# 2_Controler.net
KiCad netlist of a schematic drawn in Altium Designer
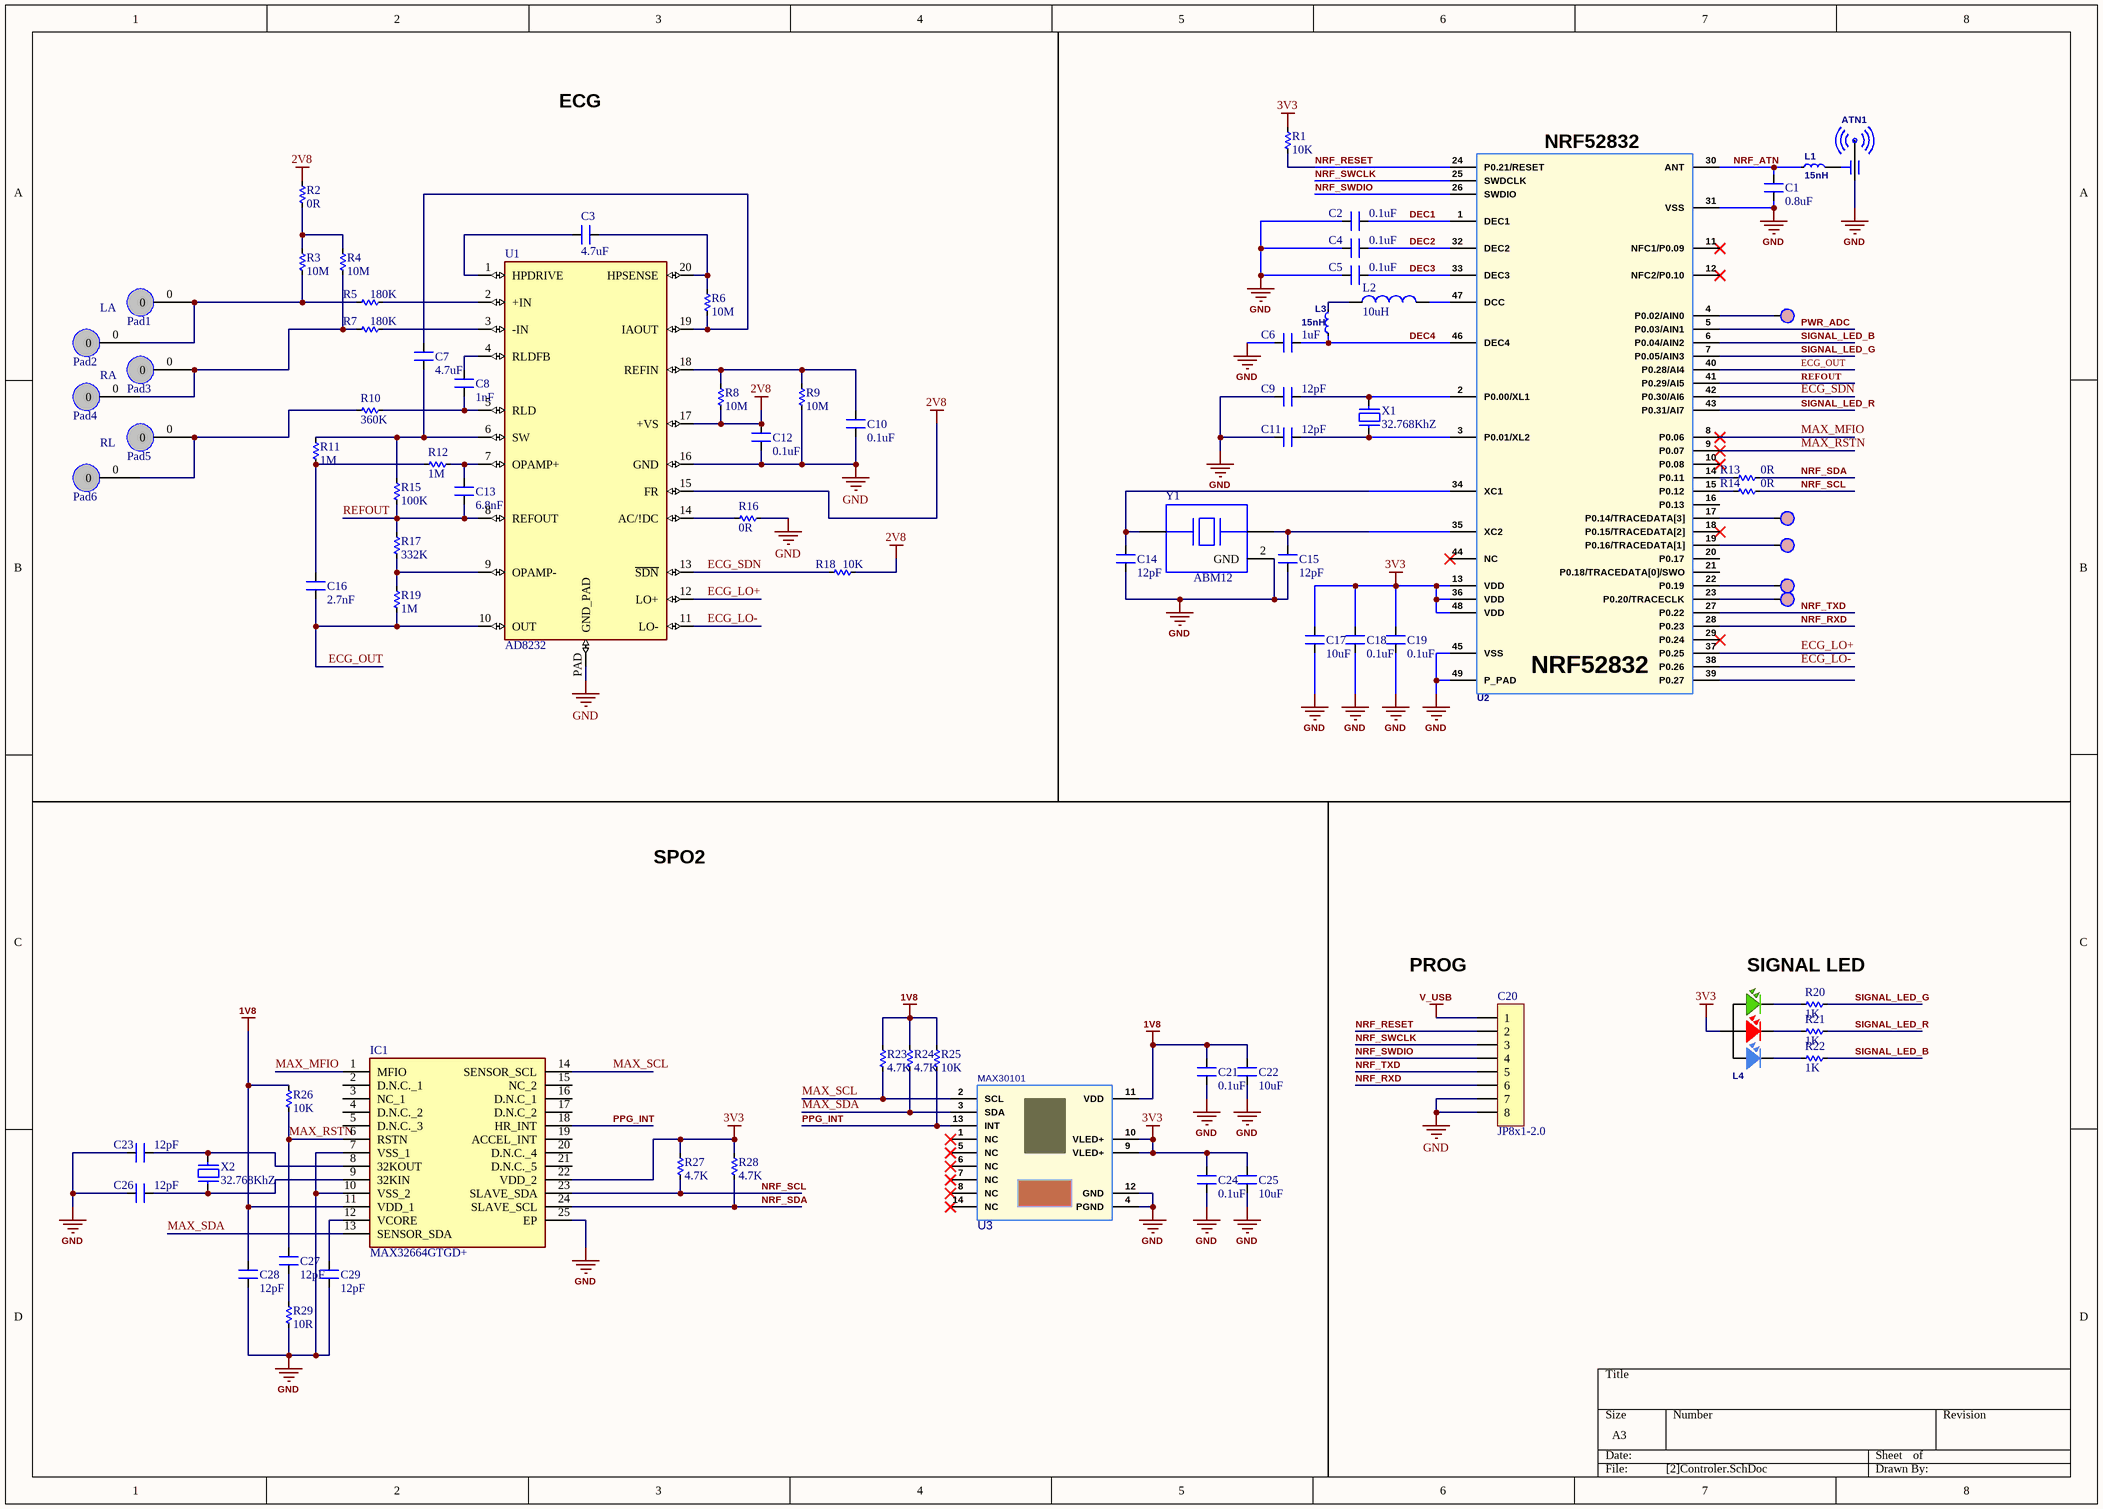
[diagram p0: [2]Controler.SchDoc]

(export (version "E")
  (design (tool "Eeschema 10.0.6"))
  (components
    (comp (ref "ATN1")
      (value "P-ANT")
      (footprint "Antenna 2G4")
      (libsource (lib "VitalSignal EcgPpg Board") (part "P-ANT"))
    )
    (comp (ref "C1")
      (value "0.8uF")
      (footprint "CN-SMD-0603")
      (description "Tu gom")
      (libsource (lib "LIBTanCN") (part "CN"))
    )
    (comp (ref "C2")
      (value "0.1uF")
      (footprint "CN-SMD-0603")
      (description "Tu gom")
      (libsource (lib "LIBTanCN") (part "CN"))
    )
    (comp (ref "C3")
      (value "4.7uF")
      (footprint "CN-SMD-0603")
      (description "Tu gom")
      (libsource (lib "LIBTanCN") (part "CN"))
    )
    (comp (ref "C4")
      (value "0.1uF")
      (footprint "CN-SMD-0603")
      (description "Tu gom")
      (libsource (lib "LIBTanCN") (part "CN"))
    )
    (comp (ref "C5")
      (value "0.1uF")
      (footprint "CN-SMD-0603")
      (description "Tu gom")
      (libsource (lib "LIBTanCN") (part "CN"))
    )
    (comp (ref "C6")
      (value "1uF")
      (footprint "CN-SMD-0603")
      (description "Tu gom")
      (libsource (lib "LIBTanCN") (part "CN"))
    )
    (comp (ref "C7")
      (value "4.7uF")
      (footprint "CN-SMD-0603")
      (description "Tu gom")
      (libsource (lib "LIBTanCN") (part "CN"))
    )
    (comp (ref "C8")
      (value "1nF")
      (footprint "CN-SMD-0603")
      (description "Tu gom")
      (libsource (lib "LIBTanCN") (part "CN"))
    )
    (comp (ref "C9")
      (value "12pF")
      (footprint "CN-SMD-0603")
      (description "Tu gom")
      (libsource (lib "LIBTanCN") (part "CN"))
    )
    (comp (ref "C10")
      (value "0.1uF")
      (footprint "CN-SMD-0603")
      (description "Tu gom")
      (libsource (lib "LIBTanCN") (part "CN"))
    )
    (comp (ref "C11")
      (value "12pF")
      (footprint "CN-SMD-0603")
      (description "Tu gom")
      (libsource (lib "LIBTanCN") (part "CN"))
    )
    (comp (ref "C12")
      (value "0.1uF")
      (footprint "CN-SMD-0603")
      (description "Tu gom")
      (libsource (lib "LIBTanCN") (part "CN"))
    )
    (comp (ref "C13")
      (value "6.8nF")
      (footprint "CN-SMD-0603")
      (description "Tu gom")
      (libsource (lib "LIBTanCN") (part "CN"))
    )
    (comp (ref "C14")
      (value "12pF")
      (footprint "CN-SMD-0603")
      (description "Tu gom")
      (libsource (lib "LIBTanCN") (part "CN"))
    )
    (comp (ref "C15")
      (value "12pF")
      (footprint "CN-SMD-0603")
      (description "Tu gom")
      (libsource (lib "LIBTanCN") (part "CN"))
    )
    (comp (ref "C16")
      (value "2.7nF")
      (footprint "CN-SMD-0603")
      (description "Tu gom")
      (libsource (lib "LIBTanCN") (part "CN"))
    )
    (comp (ref "C17")
      (value "10uF")
      (footprint "CN-SMD-0603")
      (description "Tu gom")
      (libsource (lib "LIBTanCN") (part "CN"))
    )
    (comp (ref "C18")
      (value "0.1uF")
      (footprint "CN-SMD-0603")
      (description "Tu gom")
      (libsource (lib "LIBTanCN") (part "CN"))
    )
    (comp (ref "C19")
      (value "0.1uF")
      (footprint "CN-SMD-0603")
      (description "Tu gom")
      (libsource (lib "LIBTanCN") (part "CN"))
    )
    (comp (ref "C20")
      (value "JP8x1-2.0")
      (footprint "J8-D1T")
      (description "WR-PHD 2.00 mm Socket Header")
      (fields
        (field (name "MANUFACTURER") "Würth Elektronik eiSos GmbH")
        (field (name "PARTNO") "62000811821")
        (field (name "CREATED BY") "Karrer Zheng")
      )
      (libsource (lib "LIBRARY") (part "JP8x1-2.0"))
    )
    (comp (ref "C21")
      (value "0.1uF")
      (footprint "CN-SMD-0603")
      (description "Tu gom")
      (libsource (lib "LIBTanCN") (part "CN"))
    )
    (comp (ref "C22")
      (value "10uF")
      (footprint "CN-SMD-0603")
      (description "Tu gom")
      (libsource (lib "LIBTanCN") (part "CN"))
    )
    (comp (ref "C23")
      (value "12pF")
      (footprint "CN-SMD-0603")
      (description "Tu gom")
      (libsource (lib "LIBTanCN") (part "CN"))
    )
    (comp (ref "C24")
      (value "0.1uF")
      (footprint "CN-SMD-0603")
      (description "Tu gom")
      (libsource (lib "LIBTanCN") (part "CN"))
    )
    (comp (ref "C25")
      (value "10uF")
      (footprint "CN-SMD-0603")
      (description "Tu gom")
      (libsource (lib "LIBTanCN") (part "CN"))
    )
    (comp (ref "C26")
      (value "12pF")
      (footprint "CN-SMD-0603")
      (description "Tu gom")
      (libsource (lib "LIBTanCN") (part "CN"))
    )
    (comp (ref "C27")
      (value "12pF")
      (footprint "CN-SMD-0603")
      (description "Tu gom")
      (libsource (lib "LIBTanCN") (part "CN"))
    )
    (comp (ref "C28")
      (value "12pF")
      (footprint "CN-SMD-0603")
      (description "Tu gom")
      (libsource (lib "LIBTanCN") (part "CN"))
    )
    (comp (ref "C29")
      (value "12pF")
      (footprint "CN-SMD-0603")
      (description "Tu gom")
      (libsource (lib "LIBTanCN") (part "CN"))
    )
    (comp (ref "IC1")
      (value "MAX32664GTGD+")
      (footprint "SamacSys:MAX32664GTGD")
      (description "Integrated Circuit")
      (fields (field (name "MOUSER PART NUMBER") "700-MAX32664GTGD+"))
      (libsource (lib "SamacSys") (part "MAX32664GTGD+"))
    )
    (comp (ref "L1")
      (value "15nH")
      (footprint "P-INDC-0402INDC1005X60N EIA")
      (libsource (lib "VitalSignal EcgPpg Board") (part "P-INDC-0603"))
    )
    (comp (ref "L2")
      (value "10uH")
      (footprint "Inductor_0603:INDC1608X95N")
      (description "Ind Chip Shielded Multi-Layer 10uH 30% 1MHz Ferrite 50mA 0603 T/R")
      (fields (field (name "MP") "ASMCI-0603-100N-T"))
      (libsource (lib "Inductor_0603") (part "ASMCI-0603-100N-T"))
    )
    (comp (ref "L3")
      (value "15nH")
      (footprint "P-INDC-0402INDC1005X60N EIA")
      (libsource (lib "VitalSignal EcgPpg Board") (part "P-INDC-0603"))
    )
    (comp (ref "L4")
      (value "Led RGB 0603 Anot")
      (footprint "Led RGB 0603 Anode")
      (libsource (lib "Lib_Nhat_2019") (part "Led RGB 0603 Anot"))
    )
    (comp (ref "Pad1")
      (value "LA")
      (footprint "PcbLib1:pad_ecg")
      (description "pad_ecg")
      (libsource (lib "Schlib1") (part "pad_ecg"))
    )
    (comp (ref "Pad2")
      (value "LA")
      (footprint "PcbLib1:pad_ecg")
      (description "pad_ecg")
      (libsource (lib "Schlib1") (part "pad_ecg"))
    )
    (comp (ref "Pad3")
      (value "RA")
      (footprint "PcbLib1:pad_ecg")
      (description "pad_ecg")
      (libsource (lib "Schlib1") (part "pad_ecg"))
    )
    (comp (ref "Pad4")
      (value "pad_ecg")
      (footprint "PcbLib1:pad_ecg")
      (libsource (lib "Schlib1") (part "pad_ecg"))
    )
    (comp (ref "Pad5")
      (value "RL")
      (footprint "PcbLib1:pad_ecg")
      (description "pad_ecg")
      (libsource (lib "Schlib1") (part "pad_ecg"))
    )
    (comp (ref "Pad6")
      (value "pad_ecg")
      (footprint "PcbLib1:pad_ecg")
      (libsource (lib "Schlib1") (part "pad_ecg"))
    )
    (comp (ref "R1")
      (value "10K")
      (footprint "RES-SMD-0603")
      (description "Resistor")
      (fields
        (field (name "MANUFACTURER") "Generic Components")
        (field (name "PUBLISHER") "Altium Hobart Technology Centre")
      )
      (libsource (lib "LIBRARY") (part "Res-SMD"))
    )
    (comp (ref "R2")
      (value "0R")
      (footprint "RES-SMD-0603")
      (description "Resistor")
      (fields
        (field (name "MANUFACTURER") "Generic Components")
        (field (name "PUBLISHER") "Altium Hobart Technology Centre")
      )
      (libsource (lib "LIBRARY") (part "Res-SMD"))
    )
    (comp (ref "R3")
      (value "10M")
      (footprint "RES-SMD-0603")
      (description "Resistor")
      (fields
        (field (name "MANUFACTURER") "Generic Components")
        (field (name "PUBLISHER") "Altium Hobart Technology Centre")
      )
      (libsource (lib "LIBRARY") (part "Res-SMD"))
    )
    (comp (ref "R4")
      (value "10M")
      (footprint "RES-SMD-0603")
      (description "Resistor")
      (fields
        (field (name "MANUFACTURER") "Generic Components")
        (field (name "PUBLISHER") "Altium Hobart Technology Centre")
      )
      (libsource (lib "LIBRARY") (part "Res-SMD"))
    )
    (comp (ref "R5")
      (value "180K")
      (footprint "RES-SMD-0603")
      (description "Resistor")
      (fields
        (field (name "MANUFACTURER") "Generic Components")
        (field (name "PUBLISHER") "Altium Hobart Technology Centre")
      )
      (libsource (lib "LIBRARY") (part "Res-SMD"))
    )
    (comp (ref "R6")
      (value "10M")
      (footprint "RES-SMD-0603")
      (description "Resistor")
      (fields
        (field (name "MANUFACTURER") "Generic Components")
        (field (name "PUBLISHER") "Altium Hobart Technology Centre")
      )
      (libsource (lib "LIBRARY") (part "Res-SMD"))
    )
    (comp (ref "R7")
      (value "180K")
      (footprint "RES-SMD-0603")
      (description "Resistor")
      (fields
        (field (name "MANUFACTURER") "Generic Components")
        (field (name "PUBLISHER") "Altium Hobart Technology Centre")
      )
      (libsource (lib "LIBRARY") (part "Res-SMD"))
    )
    (comp (ref "R8")
      (value "10M")
      (footprint "RES-SMD-0603")
      (description "Resistor")
      (fields
        (field (name "MANUFACTURER") "Generic Components")
        (field (name "PUBLISHER") "Altium Hobart Technology Centre")
      )
      (libsource (lib "LIBRARY") (part "Res-SMD"))
    )
    (comp (ref "R9")
      (value "10M")
      (footprint "RES-SMD-0603")
      (description "Resistor")
      (fields
        (field (name "MANUFACTURER") "Generic Components")
        (field (name "PUBLISHER") "Altium Hobart Technology Centre")
      )
      (libsource (lib "LIBRARY") (part "Res-SMD"))
    )
    (comp (ref "R10")
      (value "360K")
      (footprint "RES-SMD-0603")
      (description "Resistor")
      (fields
        (field (name "MANUFACTURER") "Generic Components")
        (field (name "PUBLISHER") "Altium Hobart Technology Centre")
      )
      (libsource (lib "LIBRARY") (part "Res-SMD"))
    )
    (comp (ref "R11")
      (value "1M")
      (footprint "RES-SMD-0603")
      (description "Resistor")
      (fields
        (field (name "MANUFACTURER") "Generic Components")
        (field (name "PUBLISHER") "Altium Hobart Technology Centre")
      )
      (libsource (lib "LIBRARY") (part "Res-SMD"))
    )
    (comp (ref "R12")
      (value "1M")
      (footprint "RES-SMD-0603")
      (description "Resistor")
      (fields
        (field (name "MANUFACTURER") "Generic Components")
        (field (name "PUBLISHER") "Altium Hobart Technology Centre")
      )
      (libsource (lib "LIBRARY") (part "Res-SMD"))
    )
    (comp (ref "R13")
      (value "0R")
      (footprint "RES-SMD-0603")
      (description "Resistor")
      (fields
        (field (name "MANUFACTURER") "Generic Components")
        (field (name "PUBLISHER") "Altium Hobart Technology Centre")
      )
      (libsource (lib "LIBRARY") (part "Res-SMD"))
    )
    (comp (ref "R14")
      (value "0R")
      (footprint "RES-SMD-0603")
      (description "Resistor")
      (fields
        (field (name "MANUFACTURER") "Generic Components")
        (field (name "PUBLISHER") "Altium Hobart Technology Centre")
      )
      (libsource (lib "LIBRARY") (part "Res-SMD"))
    )
    (comp (ref "R15")
      (value "100K")
      (footprint "RES-SMD-0603")
      (description "Resistor")
      (fields
        (field (name "MANUFACTURER") "Generic Components")
        (field (name "PUBLISHER") "Altium Hobart Technology Centre")
      )
      (libsource (lib "LIBRARY") (part "Res-SMD"))
    )
    (comp (ref "R16")
      (value "0R")
      (footprint "RES-SMD-0603")
      (description "Resistor")
      (fields
        (field (name "MANUFACTURER") "Generic Components")
        (field (name "PUBLISHER") "Altium Hobart Technology Centre")
      )
      (libsource (lib "LIBRARY") (part "Res-SMD"))
    )
    (comp (ref "R17")
      (value "332K")
      (footprint "RES-SMD-0603")
      (description "Resistor")
      (fields
        (field (name "MANUFACTURER") "Generic Components")
        (field (name "PUBLISHER") "Altium Hobart Technology Centre")
      )
      (libsource (lib "LIBRARY") (part "Res-SMD"))
    )
    (comp (ref "R18")
      (value "10K")
      (footprint "RES-SMD-0603")
      (description "Resistor")
      (fields
        (field (name "MANUFACTURER") "Generic Components")
        (field (name "PUBLISHER") "Altium Hobart Technology Centre")
      )
      (libsource (lib "LIBRARY") (part "Res-SMD"))
    )
    (comp (ref "R19")
      (value "1M")
      (footprint "RES-SMD-0603")
      (description "Resistor")
      (fields
        (field (name "MANUFACTURER") "Generic Components")
        (field (name "PUBLISHER") "Altium Hobart Technology Centre")
      )
      (libsource (lib "LIBRARY") (part "Res-SMD"))
    )
    (comp (ref "R20")
      (value "1K")
      (footprint "RES-SMD-0603")
      (description "Resistor")
      (fields
        (field (name "MANUFACTURER") "Generic Components")
        (field (name "PUBLISHER") "Altium Hobart Technology Centre")
      )
      (libsource (lib "LIBRARY") (part "Res-SMD"))
    )
    (comp (ref "R21")
      (value "1K")
      (footprint "RES-SMD-0603")
      (description "Resistor")
      (fields
        (field (name "MANUFACTURER") "Generic Components")
        (field (name "PUBLISHER") "Altium Hobart Technology Centre")
      )
      (libsource (lib "LIBRARY") (part "Res-SMD"))
    )
    (comp (ref "R22")
      (value "1K")
      (footprint "RES-SMD-0603")
      (description "Resistor")
      (fields
        (field (name "MANUFACTURER") "Generic Components")
        (field (name "PUBLISHER") "Altium Hobart Technology Centre")
      )
      (libsource (lib "LIBRARY") (part "Res-SMD"))
    )
    (comp (ref "R23")
      (value "4.7K")
      (footprint "RES-SMD-0603")
      (description "Resistor")
      (fields
        (field (name "MANUFACTURER") "Generic Components")
        (field (name "PUBLISHER") "Altium Hobart Technology Centre")
      )
      (libsource (lib "LIBRARY") (part "Res-SMD"))
    )
    (comp (ref "R24")
      (value "4.7K")
      (footprint "RES-SMD-0603")
      (description "Resistor")
      (fields
        (field (name "MANUFACTURER") "Generic Components")
        (field (name "PUBLISHER") "Altium Hobart Technology Centre")
      )
      (libsource (lib "LIBRARY") (part "Res-SMD"))
    )
    (comp (ref "R25")
      (value "10K")
      (footprint "RES-SMD-0603")
      (description "Resistor")
      (fields
        (field (name "MANUFACTURER") "Generic Components")
        (field (name "PUBLISHER") "Altium Hobart Technology Centre")
      )
      (libsource (lib "LIBRARY") (part "Res-SMD"))
    )
    (comp (ref "R26")
      (value "10K")
      (footprint "RES-SMD-0603")
      (description "Resistor")
      (fields
        (field (name "MANUFACTURER") "Generic Components")
        (field (name "PUBLISHER") "Altium Hobart Technology Centre")
      )
      (libsource (lib "LIBRARY") (part "Res-SMD"))
    )
    (comp (ref "R27")
      (value "4.7K")
      (footprint "RES-SMD-0603")
      (description "Resistor")
      (fields
        (field (name "MANUFACTURER") "Generic Components")
        (field (name "PUBLISHER") "Altium Hobart Technology Centre")
      )
      (libsource (lib "LIBRARY") (part "Res-SMD"))
    )
    (comp (ref "R28")
      (value "4.7K")
      (footprint "RES-SMD-0603")
      (description "Resistor")
      (fields
        (field (name "MANUFACTURER") "Generic Components")
        (field (name "PUBLISHER") "Altium Hobart Technology Centre")
      )
      (libsource (lib "LIBRARY") (part "Res-SMD"))
    )
    (comp (ref "R29")
      (value "10R")
      (footprint "RES-SMD-0603")
      (description "Resistor")
      (fields
        (field (name "MANUFACTURER") "Generic Components")
        (field (name "PUBLISHER") "Altium Hobart Technology Centre")
      )
      (libsource (lib "LIBRARY") (part "Res-SMD"))
    )
    (comp (ref "TP1")
      (value "TP")
      (footprint "P-TP 1MM")
      (libsource (lib "VitalSignal EcgPpg Board") (part "P-TESTPOINT"))
    )
    (comp (ref "TP2")
      (value "TP")
      (footprint "P-TP 1MM")
      (libsource (lib "VitalSignal EcgPpg Board") (part "P-TESTPOINT"))
    )
    (comp (ref "TP3")
      (value "TP")
      (footprint "P-TP 1MM")
      (libsource (lib "VitalSignal EcgPpg Board") (part "P-TESTPOINT"))
    )
    (comp (ref "TP4")
      (value "TP")
      (footprint "P-TP 1MM")
      (libsource (lib "VitalSignal EcgPpg Board") (part "P-TESTPOINT"))
    )
    (comp (ref "TP5")
      (value "TP")
      (footprint "P-TP 1MM")
      (libsource (lib "VitalSignal EcgPpg Board") (part "P-TESTPOINT"))
    )
    (comp (ref "U1")
      (value "AD8232")
      (footprint "AD8232:LFCSP_20")
      (description "ECG Front End 20-LFCSP-WQ _4x4_")
      (fields (field (name "MF") "Analog Devices"))
      (libsource (lib "AD8232") (part "AD8232"))
    )
    (comp (ref "U2")
      (value "Nrf52832")
      (footprint "QFN48_NRF52832")
      (description "BLE SoC")
      (libsource (lib "VitalSignal EcgPpg Board") (part "Nrf52832"))
    )
    (comp (ref "U3")
      (value "MAX30101")
      (footprint "MAX30101")
      (description "Pulse oximeter and Heart rate sensor")
      (libsource (lib "Lib_Nhat_2019") (part "MAX30101"))
    )
    (comp (ref "X1")
      (value "32.768KhZ")
      (footprint "XT2-32.768KHz-2_V")
      (description "Crystal, 32.768 KHz, -40 to 85 degC, 3.2 x 1.5 x 0.9 mm SMD")
      (libsource (lib "LIBRARY") (part "XT2"))
    )
    (comp (ref "X2")
      (value "32.768KhZ")
      (footprint "XT2-32.768KHz-2_V")
      (description "Crystal, 32.768 KHz, -40 to 85 degC, 3.2 x 1.5 x 0.9 mm SMD")
      (libsource (lib "LIBRARY") (part "XT2"))
    )
    (comp (ref "Y1")
      (value "ABM12")
      (footprint "DFN160X120X45-4N")
      (fields (field (name "MP") "ABM12-32.000MHZ-B2X-T3"))
      (libsource (lib "ABM12-32.000MHZ-B2X-T3") (part "ABM12-32.000MHZ-B2X-T3"))
    )
  )
  (nets
    (net (code "1") (name "/DEC1") (class "Default")
      (node (ref "C2") (pin "2") (pinfunction "2_2") (pintype "passive"))
      (node (ref "U2") (pin "1") (pinfunction "DEC1_1") (pintype "passive"))
    )
    (net (code "2") (name "/DEC2") (class "Default")
      (node (ref "C4") (pin "2") (pinfunction "2_2") (pintype "passive"))
      (node (ref "U2") (pin "32") (pinfunction "DEC2_32") (pintype "passive"))
    )
    (net (code "3") (name "/DEC3") (class "Default")
      (node (ref "C5") (pin "2") (pinfunction "2_2") (pintype "passive"))
      (node (ref "U2") (pin "33") (pinfunction "DEC3_33") (pintype "passive"))
    )
    (net (code "4") (name "/DEC4") (class "Default")
      (node (ref "C6") (pin "2") (pinfunction "2_2") (pintype "passive"))
      (node (ref "L3") (pin "1") (pinfunction "1_1") (pintype "passive"))
      (node (ref "U2") (pin "46") (pinfunction "DEC4_46") (pintype "passive"))
    )
    (net (code "5") (name "/ECG_LO+") (class "Default")
      (node (ref "U1") (pin "12") (pinfunction "LO+_12") (pintype "bidirectional"))
      (node (ref "U2") (pin "37") (pinfunction "P0.25_37") (pintype "passive"))
    )
    (net (code "6") (name "/ECG_LO-") (class "Default")
      (node (ref "U1") (pin "11") (pinfunction "LO-_11") (pintype "bidirectional"))
      (node (ref "U2") (pin "38") (pinfunction "P0.26_38") (pintype "passive"))
    )
    (net (code "7") (name "/ECG_OUT") (class "Default")
      (node (ref "C16") (pin "2") (pinfunction "2_2") (pintype "passive"))
      (node (ref "R19") (pin "1") (pinfunction "1_1") (pintype "passive"))
      (node (ref "U1") (pin "10") (pinfunction "OUT_10") (pintype "bidirectional"))
      (node (ref "U2") (pin "40") (pinfunction "P0.28/AI4_40") (pintype "passive"))
    )
    (net (code "8") (name "/ECG_SDN") (class "Default")
      (node (ref "R18") (pin "1") (pinfunction "1_1") (pintype "passive"))
      (node (ref "U1") (pin "13") (pinfunction "~{SDN}_13") (pintype "bidirectional"))
      (node (ref "U2") (pin "42") (pinfunction "P0.30/AI6_42") (pintype "passive"))
    )
    (net (code "9") (name "/MAX_MFIO") (class "Default")
      (node (ref "IC1") (pin "1") (pinfunction "MFIO_1") (pintype "passive"))
      (node (ref "U2") (pin "8") (pinfunction "P0.06_8") (pintype "passive"))
    )
    (net (code "10") (name "/MAX_RSTN") (class "Default")
      (node (ref "C27") (pin "1") (pinfunction "1_1") (pintype "passive"))
      (node (ref "IC1") (pin "6") (pinfunction "RSTN_6") (pintype "passive"))
      (node (ref "R26") (pin "1") (pinfunction "1_1") (pintype "passive"))
      (node (ref "U2") (pin "9") (pinfunction "P0.07_9") (pintype "passive"))
    )
    (net (code "11") (name "/MAX_SCL") (class "Default")
      (node (ref "IC1") (pin "14") (pinfunction "SENSOR_SCL_14") (pintype "passive"))
      (node (ref "R23") (pin "1") (pinfunction "1_1") (pintype "passive"))
      (node (ref "U3") (pin "2") (pinfunction "SCL_2") (pintype "passive"))
    )
    (net (code "12") (name "/MAX_SDA") (class "Default")
      (node (ref "IC1") (pin "13") (pinfunction "SENSOR_SDA_13") (pintype "passive"))
      (node (ref "R24") (pin "1") (pinfunction "1_1") (pintype "passive"))
      (node (ref "U3") (pin "3") (pinfunction "SDA_3") (pintype "passive"))
    )
    (net (code "13") (name "/NRF_ATN") (class "Default")
      (node (ref "C1") (pin "2") (pinfunction "2_2") (pintype "passive"))
      (node (ref "L1") (pin "1") (pinfunction "1_1") (pintype "passive"))
      (node (ref "U2") (pin "30") (pinfunction "ANT_30") (pintype "passive"))
    )
    (net (code "14") (name "/NRF_RESET") (class "Default")
      (node (ref "C20") (pin "2") (pinfunction "2_2") (pintype "passive"))
      (node (ref "R1") (pin "1") (pinfunction "1_1") (pintype "passive"))
      (node (ref "U2") (pin "24") (pinfunction "P0.21/RESET_24") (pintype "passive"))
    )
    (net (code "15") (name "/NRF_RXD") (class "Default")
      (node (ref "C20") (pin "6") (pinfunction "6_6") (pintype "passive"))
      (node (ref "U2") (pin "28") (pinfunction "P0.23_28") (pintype "passive"))
    )
    (net (code "16") (name "/NRF_SCL") (class "Default")
      (node (ref "IC1") (pin "23") (pinfunction "SLAVE_SDA_23") (pintype "passive"))
      (node (ref "R14") (pin "1") (pinfunction "1_1") (pintype "passive"))
      (node (ref "R27") (pin "1") (pinfunction "1_1") (pintype "passive"))
    )
    (net (code "17") (name "/NRF_SDA") (class "Default")
      (node (ref "IC1") (pin "24") (pinfunction "SLAVE_SCL_24") (pintype "passive"))
      (node (ref "R13") (pin "1") (pinfunction "1_1") (pintype "passive"))
      (node (ref "R28") (pin "1") (pinfunction "1_1") (pintype "passive"))
    )
    (net (code "18") (name "/NRF_SWCLK") (class "Default")
      (node (ref "C20") (pin "3") (pinfunction "3_3") (pintype "passive"))
      (node (ref "U2") (pin "25") (pinfunction "SWDCLK_25") (pintype "passive"))
    )
    (net (code "19") (name "/NRF_SWDIO") (class "Default")
      (node (ref "C20") (pin "4") (pinfunction "4_4") (pintype "passive"))
      (node (ref "U2") (pin "26") (pinfunction "SWDIO_26") (pintype "passive"))
    )
    (net (code "20") (name "/NRF_TXD") (class "Default")
      (node (ref "C20") (pin "5") (pinfunction "5_5") (pintype "passive"))
      (node (ref "U2") (pin "27") (pinfunction "P0.22_27") (pintype "passive"))
    )
    (net (code "21") (name "/PPG_INT") (class "Default")
      (node (ref "IC1") (pin "18") (pinfunction "HR_INT_18") (pintype "passive"))
      (node (ref "R25") (pin "1") (pinfunction "1_1") (pintype "passive"))
      (node (ref "U3") (pin "13") (pinfunction "INT_13") (pintype "passive"))
    )
    (net (code "22") (name "/PWR_ADC") (class "Default")
      (node (ref "U2") (pin "5") (pinfunction "P0.03/AIN1_5") (pintype "passive"))
    )
    (net (code "23") (name "/REFOUT") (class "Default")
      (node (ref "C13") (pin "2") (pinfunction "2_2") (pintype "passive"))
      (node (ref "R15") (pin "1") (pinfunction "1_1") (pintype "passive"))
      (node (ref "R17") (pin "2") (pinfunction "2_2") (pintype "passive"))
      (node (ref "U1") (pin "8") (pinfunction "REFOUT_8") (pintype "bidirectional"))
      (node (ref "U2") (pin "41") (pinfunction "P0.29/AI5_41") (pintype "passive"))
    )
    (net (code "24") (name "/SIGNAL_LED_B") (class "Default")
      (node (ref "R22") (pin "2") (pinfunction "2_2") (pintype "passive"))
      (node (ref "U2") (pin "6") (pinfunction "P0.04/AIN2_6") (pintype "passive"))
    )
    (net (code "25") (name "/SIGNAL_LED_G") (class "Default")
      (node (ref "R20") (pin "2") (pinfunction "2_2") (pintype "passive"))
      (node (ref "U2") (pin "7") (pinfunction "P0.05/AIN3_7") (pintype "passive"))
    )
    (net (code "26") (name "/SIGNAL_LED_R") (class "Default")
      (node (ref "R21") (pin "2") (pinfunction "2_2") (pintype "passive"))
      (node (ref "U2") (pin "43") (pinfunction "P0.31/AI7_43") (pintype "passive"))
    )
    (net (code "27") (name "1V8") (class "Default")
      (node (ref "C21") (pin "2") (pinfunction "2_2") (pintype "passive"))
      (node (ref "C22") (pin "2") (pinfunction "2_2") (pintype "passive"))
      (node (ref "C28") (pin "1") (pinfunction "1_1") (pintype "passive"))
      (node (ref "IC1") (pin "11") (pinfunction "VDD_1_11") (pintype "passive"))
      (node (ref "R23") (pin "2") (pinfunction "2_2") (pintype "passive"))
      (node (ref "R24") (pin "2") (pinfunction "2_2") (pintype "passive"))
      (node (ref "R25") (pin "2") (pinfunction "2_2") (pintype "passive"))
      (node (ref "R26") (pin "2") (pinfunction "2_2") (pintype "passive"))
      (node (ref "U3") (pin "11") (pinfunction "VDD_11") (pintype "passive"))
    )
    (net (code "28") (name "2V8") (class "Default")
      (node (ref "C12") (pin "2") (pinfunction "2_2") (pintype "passive"))
      (node (ref "R18") (pin "2") (pinfunction "2_2") (pintype "passive"))
      (node (ref "R2") (pin "1") (pinfunction "1_1") (pintype "passive"))
      (node (ref "R8") (pin "2") (pinfunction "2_2") (pintype "passive"))
      (node (ref "U1") (pin "15") (pinfunction "FR_15") (pintype "bidirectional"))
      (node (ref "U1") (pin "17") (pinfunction "+VS_17") (pintype "bidirectional"))
    )
    (net (code "29") (name "3V3") (class "Default")
      (node (ref "C17") (pin "1") (pinfunction "1_1") (pintype "passive"))
      (node (ref "C18") (pin "1") (pinfunction "1_1") (pintype "passive"))
      (node (ref "C19") (pin "1") (pinfunction "1_1") (pintype "passive"))
      (node (ref "C24") (pin "2") (pinfunction "2_2") (pintype "passive"))
      (node (ref "C25") (pin "2") (pinfunction "2_2") (pintype "passive"))
      (node (ref "IC1") (pin "22") (pinfunction "VDD_2_22") (pintype "passive"))
      (node (ref "L4") (pin "2") (pinfunction "2_2") (pintype "passive"))
      (node (ref "R1") (pin "2") (pinfunction "2_2") (pintype "passive"))
      (node (ref "R27") (pin "2") (pinfunction "2_2") (pintype "passive"))
      (node (ref "R28") (pin "2") (pinfunction "2_2") (pintype "passive"))
      (node (ref "U2") (pin "13") (pinfunction "VDD_13") (pintype "passive"))
      (node (ref "U2") (pin "36") (pinfunction "VDD_36") (pintype "passive"))
      (node (ref "U2") (pin "48") (pinfunction "VDD_48") (pintype "passive"))
      (node (ref "U3") (pin "10") (pinfunction "VLED+_10") (pintype "passive"))
      (node (ref "U3") (pin "9") (pinfunction "VLED+_9") (pintype "passive"))
    )
    (net (code "30") (name "GND") (class "Default")
      (node (ref "ATN1") (pin "1") (pinfunction "1_1") (pintype "passive"))
      (node (ref "C1") (pin "1") (pinfunction "1_1") (pintype "passive"))
      (node (ref "C10") (pin "1") (pinfunction "1_1") (pintype "passive"))
      (node (ref "C11") (pin "2") (pinfunction "2_2") (pintype "passive"))
      (node (ref "C12") (pin "1") (pinfunction "1_1") (pintype "passive"))
      (node (ref "C14") (pin "1") (pinfunction "1_1") (pintype "passive"))
      (node (ref "C15") (pin "1") (pinfunction "1_1") (pintype "passive"))
      (node (ref "C17") (pin "2") (pinfunction "2_2") (pintype "passive"))
      (node (ref "C18") (pin "2") (pinfunction "2_2") (pintype "passive"))
      (node (ref "C19") (pin "2") (pinfunction "2_2") (pintype "passive"))
      (node (ref "C2") (pin "1") (pinfunction "1_1") (pintype "passive"))
      (node (ref "C20") (pin "7") (pinfunction "7_7") (pintype "passive"))
      (node (ref "C20") (pin "8") (pinfunction "8_8") (pintype "passive"))
      (node (ref "C21") (pin "1") (pinfunction "1_1") (pintype "passive"))
      (node (ref "C22") (pin "1") (pinfunction "1_1") (pintype "passive"))
      (node (ref "C23") (pin "2") (pinfunction "2_2") (pintype "passive"))
      (node (ref "C24") (pin "1") (pinfunction "1_1") (pintype "passive"))
      (node (ref "C25") (pin "1") (pinfunction "1_1") (pintype "passive"))
      (node (ref "C26") (pin "2") (pinfunction "2_2") (pintype "passive"))
      (node (ref "C28") (pin "2") (pinfunction "2_2") (pintype "passive"))
      (node (ref "C29") (pin "2") (pinfunction "2_2") (pintype "passive"))
      (node (ref "C4") (pin "1") (pinfunction "1_1") (pintype "passive"))
      (node (ref "C5") (pin "1") (pinfunction "1_1") (pintype "passive"))
      (node (ref "C6") (pin "1") (pinfunction "1_1") (pintype "passive"))
      (node (ref "C9") (pin "2") (pinfunction "2_2") (pintype "passive"))
      (node (ref "IC1") (pin "10") (pinfunction "VSS_2_10") (pintype "passive"))
      (node (ref "IC1") (pin "25") (pinfunction "EP_25") (pintype "passive"))
      (node (ref "IC1") (pin "7") (pinfunction "VSS_1_7") (pintype "passive"))
      (node (ref "R16") (pin "2") (pinfunction "2_2") (pintype "passive"))
      (node (ref "R29") (pin "1") (pinfunction "1_1") (pintype "passive"))
      (node (ref "R9") (pin "2") (pinfunction "2_2") (pintype "passive"))
      (node (ref "U1") (pin "16") (pinfunction "GND_16") (pintype "bidirectional"))
      (node (ref "U1") (pin "PAD") (pinfunction "GND_PAD_PAD") (pintype "bidirectional"))
      (node (ref "U2") (pin "31") (pinfunction "VSS_31") (pintype "passive"))
      (node (ref "U2") (pin "45") (pinfunction "VSS_45") (pintype "passive"))
      (node (ref "U2") (pin "49") (pinfunction "P_PAD_49") (pintype "passive"))
      (node (ref "U3") (pin "12") (pinfunction "GND_12") (pintype "passive"))
      (node (ref "U3") (pin "4") (pinfunction "PGND_4") (pintype "passive"))
      (node (ref "Y1") (pin "2") (pinfunction "GND_2") (pintype "power_in"))
    )
    (net (code "31") (name "Net-(ATN1-Pad2)") (class "Default")
      (node (ref "ATN1") (pin "2") (pinfunction "2_2") (pintype "passive"))
      (node (ref "L1") (pin "2") (pinfunction "2_2") (pintype "passive"))
    )
    (net (code "32") (name "Net-(C16-Pad1)") (class "Default")
      (node (ref "C16") (pin "1") (pinfunction "1_1") (pintype "passive"))
      (node (ref "R11") (pin "1") (pinfunction "1_1") (pintype "passive"))
      (node (ref "R12") (pin "1") (pinfunction "1_1") (pintype "passive"))
    )
    (net (code "33") (name "Net-(C27-Pad2)") (class "Default")
      (node (ref "C27") (pin "2") (pinfunction "2_2") (pintype "passive"))
      (node (ref "R29") (pin "2") (pinfunction "2_2") (pintype "passive"))
    )
    (net (code "34") (name "Net-(IC1-32KIN)") (class "Default")
      (node (ref "C26") (pin "1") (pinfunction "1_1") (pintype "passive"))
      (node (ref "IC1") (pin "9") (pinfunction "32KIN_9") (pintype "passive"))
      (node (ref "X2") (pin "1") (pinfunction "1_1") (pintype "passive"))
    )
    (net (code "35") (name "Net-(IC1-32KOUT)") (class "Default")
      (node (ref "C23") (pin "1") (pinfunction "1_1") (pintype "passive"))
      (node (ref "IC1") (pin "8") (pinfunction "32KOUT_8") (pintype "passive"))
      (node (ref "X2") (pin "2") (pinfunction "2_2") (pintype "passive"))
    )
    (net (code "36") (name "Net-(IC1-VCORE)") (class "Default")
      (node (ref "C29") (pin "1") (pinfunction "1_1") (pintype "passive"))
      (node (ref "IC1") (pin "12") (pinfunction "VCORE_12") (pintype "passive"))
    )
    (net (code "37") (name "Net-(L2-Pad1)") (class "Default")
      (node (ref "L2") (pin "1") (pinfunction "1_1") (pintype "passive"))
      (node (ref "L3") (pin "2") (pinfunction "2_2") (pintype "passive"))
    )
    (net (code "38") (name "Net-(L4-Pad1)") (class "Default")
      (node (ref "L4") (pin "1") (pinfunction "1_1") (pintype "passive"))
      (node (ref "R21") (pin "1") (pinfunction "1_1") (pintype "passive"))
    )
    (net (code "39") (name "Net-(L4-Pad3)") (class "Default")
      (node (ref "L4") (pin "3") (pinfunction "3_3") (pintype "passive"))
      (node (ref "R22") (pin "1") (pinfunction "1_1") (pintype "passive"))
    )
    (net (code "40") (name "Net-(L4-Pad4)") (class "Default")
      (node (ref "L4") (pin "4") (pinfunction "4_4") (pintype "passive"))
      (node (ref "R20") (pin "1") (pinfunction "1_1") (pintype "passive"))
    )
    (net (code "41") (name "Net-(Pad1-Pad0)") (class "Default")
      (node (ref "Pad1") (pin "0") (pinfunction "0_0") (pintype "passive"))
      (node (ref "Pad2") (pin "0") (pinfunction "0_0") (pintype "passive"))
      (node (ref "R3") (pin "2") (pinfunction "2_2") (pintype "passive"))
      (node (ref "R5") (pin "1") (pinfunction "1_1") (pintype "passive"))
    )
    (net (code "42") (name "Net-(Pad3-Pad0)") (class "Default")
      (node (ref "Pad3") (pin "0") (pinfunction "0_0") (pintype "passive"))
      (node (ref "Pad4") (pin "0") (pinfunction "0_0") (pintype "passive"))
      (node (ref "R4") (pin "2") (pinfunction "2_2") (pintype "passive"))
      (node (ref "R7") (pin "1") (pinfunction "1_1") (pintype "passive"))
    )
    (net (code "43") (name "Net-(Pad5-Pad0)") (class "Default")
      (node (ref "Pad5") (pin "0") (pinfunction "0_0") (pintype "passive"))
      (node (ref "Pad6") (pin "0") (pinfunction "0_0") (pintype "passive"))
      (node (ref "R10") (pin "1") (pinfunction "1_1") (pintype "passive"))
    )
    (net (code "44") (name "Net-(R2-Pad2)") (class "Default")
      (node (ref "R2") (pin "2") (pinfunction "2_2") (pintype "passive"))
      (node (ref "R3") (pin "1") (pinfunction "1_1") (pintype "passive"))
      (node (ref "R4") (pin "1") (pinfunction "1_1") (pintype "passive"))
    )
    (net (code "45") (name "Net-(U1-+IN)") (class "Default")
      (node (ref "R5") (pin "2") (pinfunction "2_2") (pintype "passive"))
      (node (ref "U1") (pin "2") (pinfunction "+IN_2") (pintype "bidirectional"))
    )
    (net (code "46") (name "Net-(U1--IN)") (class "Default")
      (node (ref "R7") (pin "2") (pinfunction "2_2") (pintype "passive"))
      (node (ref "U1") (pin "3") (pinfunction "-IN_3") (pintype "bidirectional"))
    )
    (net (code "47") (name "Net-(U1-AC{slash}!DC)") (class "Default")
      (node (ref "R16") (pin "1") (pinfunction "1_1") (pintype "passive"))
      (node (ref "U1") (pin "14") (pinfunction "AC/!DC_14") (pintype "bidirectional"))
    )
    (net (code "48") (name "Net-(U1-HPDRIVE)") (class "Default")
      (node (ref "C3") (pin "2") (pinfunction "2_2") (pintype "passive"))
      (node (ref "U1") (pin "1") (pinfunction "HPDRIVE_1") (pintype "bidirectional"))
    )
    (net (code "49") (name "Net-(U1-HPSENSE)") (class "Default")
      (node (ref "C3") (pin "1") (pinfunction "1_1") (pintype "passive"))
      (node (ref "R6") (pin "1") (pinfunction "1_1") (pintype "passive"))
      (node (ref "U1") (pin "20") (pinfunction "HPSENSE_20") (pintype "bidirectional"))
    )
    (net (code "50") (name "Net-(U1-IAOUT)") (class "Default")
      (node (ref "C7") (pin "1") (pinfunction "1_1") (pintype "passive"))
      (node (ref "R6") (pin "2") (pinfunction "2_2") (pintype "passive"))
      (node (ref "U1") (pin "19") (pinfunction "IAOUT_19") (pintype "bidirectional"))
    )
    (net (code "51") (name "Net-(U1-OPAMP+)") (class "Default")
      (node (ref "C13") (pin "1") (pinfunction "1_1") (pintype "passive"))
      (node (ref "R12") (pin "2") (pinfunction "2_2") (pintype "passive"))
      (node (ref "U1") (pin "7") (pinfunction "OPAMP+_7") (pintype "bidirectional"))
    )
    (net (code "52") (name "Net-(U1-OPAMP-)") (class "Default")
      (node (ref "R17") (pin "1") (pinfunction "1_1") (pintype "passive"))
      (node (ref "R19") (pin "2") (pinfunction "2_2") (pintype "passive"))
      (node (ref "U1") (pin "9") (pinfunction "OPAMP-_9") (pintype "bidirectional"))
    )
    (net (code "53") (name "Net-(U1-REFIN)") (class "Default")
      (node (ref "C10") (pin "2") (pinfunction "2_2") (pintype "passive"))
      (node (ref "R8") (pin "1") (pinfunction "1_1") (pintype "passive"))
      (node (ref "R9") (pin "1") (pinfunction "1_1") (pintype "passive"))
      (node (ref "U1") (pin "18") (pinfunction "REFIN_18") (pintype "bidirectional"))
    )
    (net (code "54") (name "Net-(U1-RLD)") (class "Default")
      (node (ref "C8") (pin "2") (pinfunction "2_2") (pintype "passive"))
      (node (ref "R10") (pin "2") (pinfunction "2_2") (pintype "passive"))
      (node (ref "U1") (pin "5") (pinfunction "RLD_5") (pintype "bidirectional"))
    )
    (net (code "55") (name "Net-(U1-RLDFB)") (class "Default")
      (node (ref "C8") (pin "1") (pinfunction "1_1") (pintype "passive"))
      (node (ref "U1") (pin "4") (pinfunction "RLDFB_4") (pintype "bidirectional"))
    )
    (net (code "56") (name "Net-(U1-SW)") (class "Default")
      (node (ref "C7") (pin "2") (pinfunction "2_2") (pintype "passive"))
      (node (ref "R11") (pin "2") (pinfunction "2_2") (pintype "passive"))
      (node (ref "R15") (pin "2") (pinfunction "2_2") (pintype "passive"))
      (node (ref "U1") (pin "6") (pinfunction "SW_6") (pintype "bidirectional"))
    )
    (net (code "57") (name "Net-(U2-DCC)") (class "Default")
      (node (ref "L2") (pin "2") (pinfunction "2_2") (pintype "passive"))
      (node (ref "U2") (pin "47") (pinfunction "DCC_47") (pintype "passive"))
    )
    (net (code "58") (name "Net-(U2-P0.00{slash}XL1)") (class "Default")
      (node (ref "C9") (pin "1") (pinfunction "1_1") (pintype "passive"))
      (node (ref "U2") (pin "2") (pinfunction "P0.00/XL1_2") (pintype "passive"))
      (node (ref "X1") (pin "2") (pinfunction "2_2") (pintype "passive"))
    )
    (net (code "59") (name "Net-(U2-P0.01{slash}XL2)") (class "Default")
      (node (ref "C11") (pin "1") (pinfunction "1_1") (pintype "passive"))
      (node (ref "U2") (pin "3") (pinfunction "P0.01/XL2_3") (pintype "passive"))
      (node (ref "X1") (pin "1") (pinfunction "1_1") (pintype "passive"))
    )
    (net (code "60") (name "Net-(U2-P0.02{slash}AIN0)") (class "Default")
      (node (ref "TP1") (pin "1") (pinfunction "1_1") (pintype "passive"))
      (node (ref "U2") (pin "4") (pinfunction "P0.02/AIN0_4") (pintype "passive"))
    )
    (net (code "61") (name "Net-(U2-P0.11)") (class "Default")
      (node (ref "R13") (pin "2") (pinfunction "2_2") (pintype "passive"))
      (node (ref "U2") (pin "14") (pinfunction "P0.11_14") (pintype "passive"))
    )
    (net (code "62") (name "Net-(U2-P0.12)") (class "Default")
      (node (ref "R14") (pin "2") (pinfunction "2_2") (pintype "passive"))
      (node (ref "U2") (pin "15") (pinfunction "P0.12_15") (pintype "passive"))
    )
    (net (code "63") (name "Net-(U2-P0.14{slash}TRACEDATA[3])") (class "Default")
      (node (ref "TP2") (pin "1") (pinfunction "1_1") (pintype "passive"))
      (node (ref "U2") (pin "17") (pinfunction "P0.14/TRACEDATA[3]_17") (pintype "passive"))
    )
    (net (code "64") (name "Net-(U2-P0.16{slash}TRACEDATA[1])") (class "Default")
      (node (ref "TP3") (pin "1") (pinfunction "1_1") (pintype "passive"))
      (node (ref "U2") (pin "19") (pinfunction "P0.16/TRACEDATA[1]_19") (pintype "passive"))
    )
    (net (code "65") (name "Net-(U2-P0.19)") (class "Default")
      (node (ref "TP4") (pin "1") (pinfunction "1_1") (pintype "passive"))
      (node (ref "U2") (pin "22") (pinfunction "P0.19_22") (pintype "passive"))
    )
    (net (code "66") (name "Net-(U2-P0.20{slash}TRACECLK)") (class "Default")
      (node (ref "TP5") (pin "1") (pinfunction "1_1") (pintype "passive"))
      (node (ref "U2") (pin "23") (pinfunction "P0.20/TRACECLK_23") (pintype "passive"))
    )
    (net (code "67") (name "Net-(U2-XC1)") (class "Default")
      (node (ref "C14") (pin "2") (pinfunction "2_2") (pintype "passive"))
      (node (ref "U2") (pin "34") (pinfunction "XC1_34") (pintype "passive"))
      (node (ref "Y1") (pin "1") (pinfunction "1_1") (pintype "passive"))
    )
    (net (code "68") (name "Net-(U2-XC2)") (class "Default")
      (node (ref "C15") (pin "2") (pinfunction "2_2") (pintype "passive"))
      (node (ref "U2") (pin "35") (pinfunction "XC2_35") (pintype "passive"))
      (node (ref "Y1") (pin "3") (pinfunction "2_3") (pintype "passive"))
    )
    (net (code "69") (name "V_USB") (class "Default")
      (node (ref "C20") (pin "1") (pinfunction "1_1") (pintype "passive"))
    )
    (net (code "70") (name "unconnected-(IC1-ACCEL_INT-Pad19)") (class "Default")
      (node (ref "IC1") (pin "19") (pinfunction "ACCEL_INT_19") (pintype "passive"))
    )
    (net (code "71") (name "unconnected-(IC1-D.N.C._1-Pad2)") (class "Default")
      (node (ref "IC1") (pin "2") (pinfunction "D.N.C._1_2") (pintype "passive"))
    )
    (net (code "72") (name "unconnected-(IC1-D.N.C._2-Pad4)") (class "Default")
      (node (ref "IC1") (pin "4") (pinfunction "D.N.C._2_4") (pintype "passive"))
    )
    (net (code "73") (name "unconnected-(IC1-D.N.C._3-Pad5)") (class "Default")
      (node (ref "IC1") (pin "5") (pinfunction "D.N.C._3_5") (pintype "passive"))
    )
    (net (code "74") (name "unconnected-(IC1-D.N.C._4-Pad20)") (class "Default")
      (node (ref "IC1") (pin "20") (pinfunction "D.N.C._4_20") (pintype "passive"))
    )
    (net (code "75") (name "unconnected-(IC1-D.N.C._5-Pad21)") (class "Default")
      (node (ref "IC1") (pin "21") (pinfunction "D.N.C._5_21") (pintype "passive"))
    )
    (net (code "76") (name "unconnected-(IC1-D.N.C_1-Pad16)") (class "Default")
      (node (ref "IC1") (pin "16") (pinfunction "D.N.C_1_16") (pintype "passive"))
    )
    (net (code "77") (name "unconnected-(IC1-D.N.C_2-Pad17)") (class "Default")
      (node (ref "IC1") (pin "17") (pinfunction "D.N.C_2_17") (pintype "passive"))
    )
    (net (code "78") (name "unconnected-(IC1-NC_1-Pad3)") (class "Default")
      (node (ref "IC1") (pin "3") (pinfunction "NC_1_3") (pintype "passive"))
    )
    (net (code "79") (name "unconnected-(IC1-NC_2-Pad15)") (class "Default")
      (node (ref "IC1") (pin "15") (pinfunction "NC_2_15") (pintype "passive"))
    )
    (net (code "80") (name "unconnected-(L4-Pad2)") (class "Default")
      (node (ref "L4") (pin "2") (pinfunction "2_2") (pintype "passive"))
    )
    (net (code "81") (name "unconnected-(U2-NC-Pad44)") (class "Default")
      (node (ref "U2") (pin "44") (pinfunction "NC_44") (pintype "passive+no_connect"))
    )
    (net (code "82") (name "unconnected-(U2-NFC1{slash}P0.09-Pad11)") (class "Default")
      (node (ref "U2") (pin "11") (pinfunction "NFC1/P0.09_11") (pintype "passive+no_connect"))
    )
    (net (code "83") (name "unconnected-(U2-NFC2{slash}P0.10-Pad12)") (class "Default")
      (node (ref "U2") (pin "12") (pinfunction "NFC2/P0.10_12") (pintype "passive+no_connect"))
    )
    (net (code "84") (name "unconnected-(U2-P0.08-Pad10)") (class "Default")
      (node (ref "U2") (pin "10") (pinfunction "P0.08_10") (pintype "passive+no_connect"))
    )
    (net (code "85") (name "unconnected-(U2-P0.13-Pad16)") (class "Default")
      (node (ref "U2") (pin "16") (pinfunction "P0.13_16") (pintype "passive"))
    )
    (net (code "86") (name "unconnected-(U2-P0.15{slash}TRACEDATA[2]-Pad18)") (class "Default")
      (node (ref "U2") (pin "18") (pinfunction "P0.15/TRACEDATA[2]_18") (pintype "passive+no_connect"))
    )
    (net (code "87") (name "unconnected-(U2-P0.17-Pad20)") (class "Default")
      (node (ref "U2") (pin "20") (pinfunction "P0.17_20") (pintype "passive"))
    )
    (net (code "88") (name "unconnected-(U2-P0.18{slash}TRACEDATA[0]{slash}SWO-Pad21)") (class "Default")
      (node (ref "U2") (pin "21") (pinfunction "P0.18/TRACEDATA[0]/SWO_21") (pintype "passive"))
    )
    (net (code "89") (name "unconnected-(U2-P0.24-Pad29)") (class "Default")
      (node (ref "U2") (pin "29") (pinfunction "P0.24_29") (pintype "passive+no_connect"))
    )
    (net (code "90") (name "unconnected-(U2-P0.27-Pad39)") (class "Default")
      (node (ref "U2") (pin "39") (pinfunction "P0.27_39") (pintype "passive"))
    )
    (net (code "91") (name "unconnected-(U3-NC-Pad1)") (class "Default")
      (node (ref "U3") (pin "1") (pinfunction "NC_1") (pintype "passive+no_connect"))
    )
    (net (code "92") (name "unconnected-(U3-NC-Pad5)") (class "Default")
      (node (ref "U3") (pin "5") (pinfunction "NC_5") (pintype "passive+no_connect"))
    )
    (net (code "93") (name "unconnected-(U3-NC-Pad6)") (class "Default")
      (node (ref "U3") (pin "6") (pinfunction "NC_6") (pintype "passive+no_connect"))
    )
    (net (code "94") (name "unconnected-(U3-NC-Pad7)") (class "Default")
      (node (ref "U3") (pin "7") (pinfunction "NC_7") (pintype "passive+no_connect"))
    )
    (net (code "95") (name "unconnected-(U3-NC-Pad8)") (class "Default")
      (node (ref "U3") (pin "8") (pinfunction "NC_8") (pintype "passive+no_connect"))
    )
    (net (code "96") (name "unconnected-(U3-NC-Pad14)") (class "Default")
      (node (ref "U3") (pin "14") (pinfunction "NC_14") (pintype "passive+no_connect"))
    )
  )
)
